# mic-preamp1.net
KiCad netlist of a schematic drawn in EAGLE
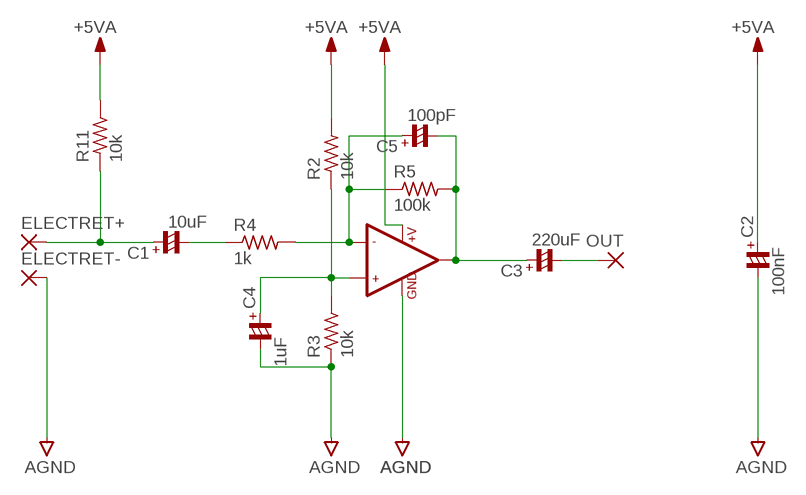
[diagram p0: schematic, sheet 1]

(export (version "E")
  (design (tool "Eeschema 10.0.6"))
  (components
    (comp (ref "C1")
      (value "10uF")
      (footprint "eagle-import:E5-4")
      (libsource (lib "eagle-import") (part "CPOL-USE5-4"))
    )
    (comp (ref "C2")
      (value "100nF")
      (footprint "eagle-import:E5-4")
      (libsource (lib "eagle-import") (part "CPOL-USE5-4"))
    )
    (comp (ref "C3")
      (value "220uF")
      (footprint "eagle-import:E5-4")
      (libsource (lib "eagle-import") (part "CPOL-USE5-4"))
    )
    (comp (ref "C4")
      (value "1uF")
      (footprint "eagle-import:E5-4")
      (libsource (lib "eagle-import") (part "CPOL-USE5-4"))
    )
    (comp (ref "C5")
      (value "100pF")
      (footprint "eagle-import:E5-4")
      (libsource (lib "eagle-import") (part "CPOL-USE5-4"))
    )
    (comp (ref "ELECTRET+")
      (value "1,6/0,9")
      (footprint "eagle-import:1,6_0,9")
      (libsource (lib "eagle-import") (part "1,6/0,9"))
    )
    (comp (ref "ELECTRET-")
      (value "1,6/0,9")
      (footprint "eagle-import:1,6_0,9")
      (libsource (lib "eagle-import") (part "1,6/0,9"))
    )
    (comp (ref "OUT")
      (value "1,6/0,9")
      (footprint "eagle-import:1,6_0,9")
      (libsource (lib "eagle-import") (part "1,6/0,9"))
    )
    (comp (ref "R2")
      (value "10k")
      (footprint "eagle-import:0204_5")
      (libsource (lib "eagle-import") (part "R-US_0204/5"))
    )
    (comp (ref "R3")
      (value "10k")
      (footprint "eagle-import:0204_5")
      (libsource (lib "eagle-import") (part "R-US_0204/5"))
    )
    (comp (ref "R4")
      (value "1k")
      (footprint "eagle-import:0204_5")
      (libsource (lib "eagle-import") (part "R-US_0204/5"))
    )
    (comp (ref "R5")
      (value "100k")
      (footprint "eagle-import:0204_5")
      (libsource (lib "eagle-import") (part "R-US_0204/5"))
    )
    (comp (ref "R11")
      (value "10k")
      (footprint "eagle-import:0204_5")
      (libsource (lib "eagle-import") (part "R-US_0204/5"))
    )
    (comp (ref "U$1")
      (value "LMV358")
      (footprint "eagle-import:SO08")
      (libsource (lib "eagle-import") (part "LMV358"))
    )
  )
  (nets
    (net (code "1") (name "+5VA") (class "Default")
      (node (ref "C2") (pin "+") (pinfunction "+_+") (pintype "passive"))
      (node (ref "R11") (pin "2") (pinfunction "2_2") (pintype "passive"))
      (node (ref "R2") (pin "2") (pinfunction "2_2") (pintype "passive"))
      (node (ref "U$1") (pin "8") (pinfunction "+V_8") (pintype "power_in"))
    )
    (net (code "2") (name "AGND") (class "Default")
      (node (ref "C2") (pin "-") (pinfunction "-_-") (pintype "passive"))
      (node (ref "C4") (pin "-") (pinfunction "-_-") (pintype "passive"))
      (node (ref "ELECTRET-") (pin "1") (pinfunction "P_1") (pintype "passive"))
      (node (ref "R3") (pin "1") (pinfunction "1_1") (pintype "passive"))
      (node (ref "U$1") (pin "4") (pinfunction "GND_4") (pintype "power_in"))
    )
    (net (code "3") (name "Net-(C1-Pad-)") (class "Default")
      (node (ref "C1") (pin "-") (pinfunction "-_-") (pintype "passive"))
      (node (ref "R4") (pin "1") (pinfunction "1_1") (pintype "passive"))
    )
    (net (code "4") (name "Net-(ELECTRET+-P)") (class "Default")
      (node (ref "C1") (pin "+") (pinfunction "+_+") (pintype "passive"))
      (node (ref "ELECTRET+") (pin "1") (pinfunction "P_1") (pintype "passive"))
      (node (ref "R11") (pin "1") (pinfunction "1_1") (pintype "passive"))
    )
    (net (code "5") (name "Net-(OUT-P)") (class "Default")
      (node (ref "C3") (pin "-") (pinfunction "-_-") (pintype "passive"))
      (node (ref "OUT") (pin "1") (pinfunction "P_1") (pintype "passive"))
    )
    (net (code "6") (name "Net-(U$1A-+IN1)") (class "Default")
      (node (ref "C4") (pin "+") (pinfunction "+_+") (pintype "passive"))
      (node (ref "R2") (pin "1") (pinfunction "1_1") (pintype "passive"))
      (node (ref "R3") (pin "2") (pinfunction "2_2") (pintype "passive"))
      (node (ref "U$1") (pin "3") (pinfunction "+IN1_3") (pintype "input"))
    )
    (net (code "7") (name "Net-(U$1A--IN1)") (class "Default")
      (node (ref "C5") (pin "+") (pinfunction "+_+") (pintype "passive"))
      (node (ref "R4") (pin "2") (pinfunction "2_2") (pintype "passive"))
      (node (ref "R5") (pin "1") (pinfunction "1_1") (pintype "passive"))
      (node (ref "U$1") (pin "2") (pinfunction "-IN1_2") (pintype "input"))
    )
    (net (code "8") (name "Net-(U$1A-OUT1)") (class "Default")
      (node (ref "C3") (pin "+") (pinfunction "+_+") (pintype "passive"))
      (node (ref "C5") (pin "-") (pinfunction "-_-") (pintype "passive"))
      (node (ref "R5") (pin "2") (pinfunction "2_2") (pintype "passive"))
      (node (ref "U$1") (pin "1") (pinfunction "OUT1_1") (pintype "output"))
    )
  )
)
